# ProDoc_T527_LPDDR4_8__2024-06-06.net
KiCad netlist of a schematic drawn in EasyEDA Pro
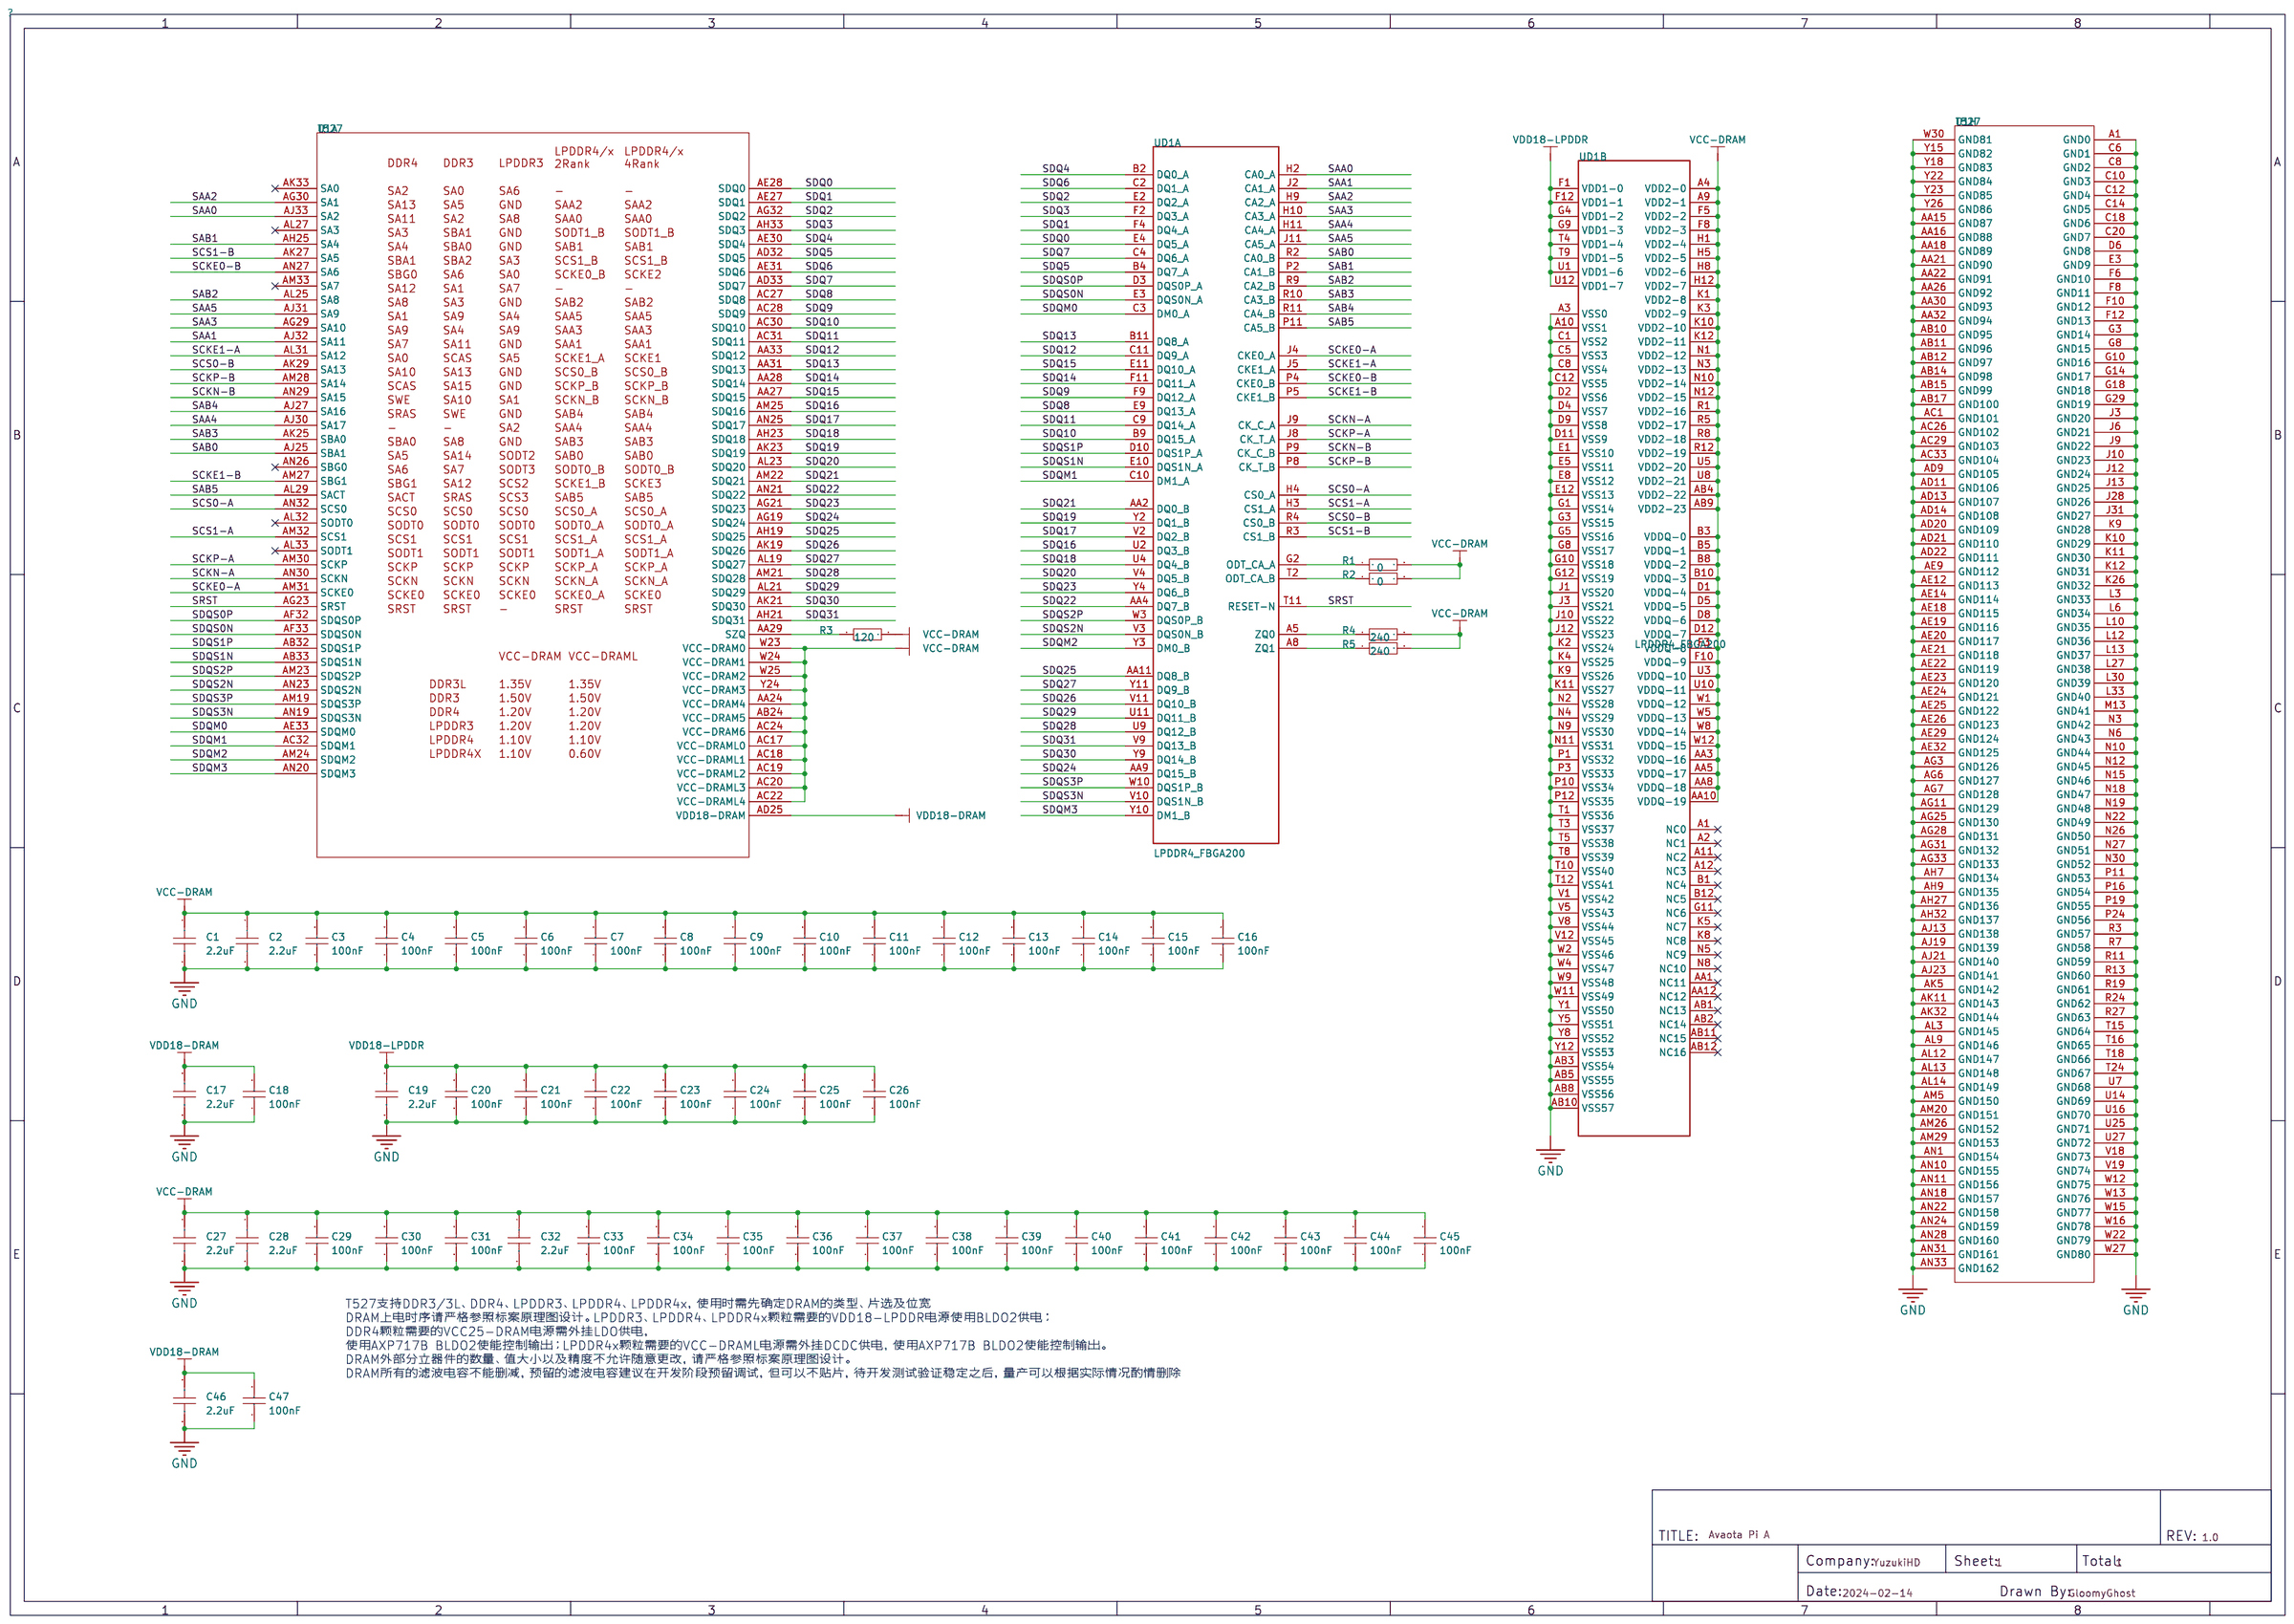
[diagram p0: schematic sheet]

(export (version "E")
  (design (tool "Eeschema 10.0.6"))
  (components
    (comp (ref "C1")
      (value "2.2uF")
      (footprint "easyedapro:C0201")
      (description "容值:2.2uF;精度:±20%;额定电压:6.3V;材质(温度系数):X5R;")
      (fields (field (name "Manufacturer Part") "0201X225M6R3NT") (field (name "Manufacturer") "FH(风华)"))
      (libsource (lib "easyedapro") (part "0201X225M6R3NT"))
    )
    (comp (ref "C2")
      (value "2.2uF")
      (footprint "easyedapro:C0201")
      (description "容值:2.2uF;精度:±20%;额定电压:6.3V;材质(温度系数):X5R;")
      (fields (field (name "Manufacturer Part") "0201X225M6R3NT") (field (name "Manufacturer") "FH(风华)"))
      (libsource (lib "easyedapro") (part "0201X225M6R3NT"))
    )
    (comp (ref "C3")
      (value "100nF")
      (footprint "easyedapro:C0201")
      (description "容值:100nF;精度:±10%;额定电压:10V;材质(温度系数):X5R;")
      (fields
        (field (name "Manufacturer Part") "GRM033R61A104KE15D")
        (field (name "Manufacturer") "muRata(村田)")
      )
      (libsource (lib "easyedapro") (part "GRM033R61A104KE15D"))
    )
    (comp (ref "C4")
      (value "100nF")
      (footprint "easyedapro:C0201")
      (description "容值:100nF;精度:±10%;额定电压:10V;材质(温度系数):X5R;")
      (fields
        (field (name "Manufacturer Part") "GRM033R61A104KE15D")
        (field (name "Manufacturer") "muRata(村田)")
      )
      (libsource (lib "easyedapro") (part "GRM033R61A104KE15D"))
    )
    (comp (ref "C5")
      (value "100nF")
      (footprint "easyedapro:C0201")
      (description "容值:100nF;精度:±10%;额定电压:10V;材质(温度系数):X5R;")
      (fields
        (field (name "Manufacturer Part") "GRM033R61A104KE15D")
        (field (name "Manufacturer") "muRata(村田)")
      )
      (libsource (lib "easyedapro") (part "GRM033R61A104KE15D"))
    )
    (comp (ref "C6")
      (value "100nF")
      (footprint "easyedapro:C0201")
      (description "容值:100nF;精度:±10%;额定电压:10V;材质(温度系数):X5R;")
      (fields
        (field (name "Manufacturer Part") "GRM033R61A104KE15D")
        (field (name "Manufacturer") "muRata(村田)")
      )
      (libsource (lib "easyedapro") (part "GRM033R61A104KE15D"))
    )
    (comp (ref "C7")
      (value "100nF")
      (footprint "easyedapro:C0201")
      (description "容值:100nF;精度:±10%;额定电压:10V;材质(温度系数):X5R;")
      (fields
        (field (name "Manufacturer Part") "GRM033R61A104KE15D")
        (field (name "Manufacturer") "muRata(村田)")
      )
      (libsource (lib "easyedapro") (part "GRM033R61A104KE15D"))
    )
    (comp (ref "C8")
      (value "100nF")
      (footprint "easyedapro:C0201")
      (description "容值:100nF;精度:±10%;额定电压:10V;材质(温度系数):X5R;")
      (fields
        (field (name "Manufacturer Part") "GRM033R61A104KE15D")
        (field (name "Manufacturer") "muRata(村田)")
      )
      (libsource (lib "easyedapro") (part "GRM033R61A104KE15D"))
    )
    (comp (ref "C9")
      (value "100nF")
      (footprint "easyedapro:C0201")
      (description "容值:100nF;精度:±10%;额定电压:10V;材质(温度系数):X5R;")
      (fields
        (field (name "Manufacturer Part") "GRM033R61A104KE15D")
        (field (name "Manufacturer") "muRata(村田)")
      )
      (libsource (lib "easyedapro") (part "GRM033R61A104KE15D"))
    )
    (comp (ref "C10")
      (value "100nF")
      (footprint "easyedapro:C0201")
      (description "容值:100nF;精度:±10%;额定电压:10V;材质(温度系数):X5R;")
      (fields
        (field (name "Manufacturer Part") "GRM033R61A104KE15D")
        (field (name "Manufacturer") "muRata(村田)")
      )
      (libsource (lib "easyedapro") (part "GRM033R61A104KE15D"))
    )
    (comp (ref "C11")
      (value "100nF")
      (footprint "easyedapro:C0201")
      (description "容值:100nF;精度:±10%;额定电压:10V;材质(温度系数):X5R;")
      (fields
        (field (name "Manufacturer Part") "GRM033R61A104KE15D")
        (field (name "Manufacturer") "muRata(村田)")
      )
      (libsource (lib "easyedapro") (part "GRM033R61A104KE15D"))
    )
    (comp (ref "C12")
      (value "100nF")
      (footprint "easyedapro:C0201")
      (description "容值:100nF;精度:±10%;额定电压:10V;材质(温度系数):X5R;")
      (fields
        (field (name "Manufacturer Part") "GRM033R61A104KE15D")
        (field (name "Manufacturer") "muRata(村田)")
      )
      (libsource (lib "easyedapro") (part "GRM033R61A104KE15D"))
    )
    (comp (ref "C13")
      (value "100nF")
      (footprint "easyedapro:C0201")
      (description "容值:100nF;精度:±10%;额定电压:10V;材质(温度系数):X5R;")
      (fields
        (field (name "Manufacturer Part") "GRM033R61A104KE15D")
        (field (name "Manufacturer") "muRata(村田)")
      )
      (libsource (lib "easyedapro") (part "GRM033R61A104KE15D"))
    )
    (comp (ref "C14")
      (value "100nF")
      (footprint "easyedapro:C0201")
      (description "容值:100nF;精度:±10%;额定电压:10V;材质(温度系数):X5R;")
      (fields
        (field (name "Manufacturer Part") "GRM033R61A104KE15D")
        (field (name "Manufacturer") "muRata(村田)")
      )
      (libsource (lib "easyedapro") (part "GRM033R61A104KE15D"))
    )
    (comp (ref "C15")
      (value "100nF")
      (footprint "easyedapro:C0201")
      (description "容值:100nF;精度:±10%;额定电压:10V;材质(温度系数):X5R;")
      (fields
        (field (name "Manufacturer Part") "GRM033R61A104KE15D")
        (field (name "Manufacturer") "muRata(村田)")
      )
      (libsource (lib "easyedapro") (part "GRM033R61A104KE15D"))
    )
    (comp (ref "C16")
      (value "100nF")
      (footprint "easyedapro:C0201")
      (description "容值:100nF;精度:±10%;额定电压:10V;材质(温度系数):X5R;")
      (fields
        (field (name "Manufacturer Part") "GRM033R61A104KE15D")
        (field (name "Manufacturer") "muRata(村田)")
      )
      (libsource (lib "easyedapro") (part "GRM033R61A104KE15D"))
    )
    (comp (ref "C17")
      (value "2.2uF")
      (footprint "easyedapro:C0201")
      (description "容值:2.2uF;精度:±20%;额定电压:6.3V;材质(温度系数):X5R;")
      (fields (field (name "Manufacturer Part") "0201X225M6R3NT") (field (name "Manufacturer") "FH(风华)"))
      (libsource (lib "easyedapro") (part "0201X225M6R3NT"))
    )
    (comp (ref "C18")
      (value "100nF")
      (footprint "easyedapro:C0201")
      (description "容值:100nF;精度:±10%;额定电压:10V;材质(温度系数):X5R;")
      (fields
        (field (name "Manufacturer Part") "GRM033R61A104KE15D")
        (field (name "Manufacturer") "muRata(村田)")
      )
      (libsource (lib "easyedapro") (part "GRM033R61A104KE15D"))
    )
    (comp (ref "C19")
      (value "2.2uF")
      (footprint "easyedapro:C0201")
      (description "容值:2.2uF;精度:±20%;额定电压:6.3V;材质(温度系数):X5R;")
      (fields (field (name "Manufacturer Part") "0201X225M6R3NT") (field (name "Manufacturer") "FH(风华)"))
      (libsource (lib "easyedapro") (part "0201X225M6R3NT"))
    )
    (comp (ref "C20")
      (value "100nF")
      (footprint "easyedapro:C0201")
      (description "容值:100nF;精度:±10%;额定电压:10V;材质(温度系数):X5R;")
      (fields
        (field (name "Manufacturer Part") "GRM033R61A104KE15D")
        (field (name "Manufacturer") "muRata(村田)")
      )
      (libsource (lib "easyedapro") (part "GRM033R61A104KE15D"))
    )
    (comp (ref "C21")
      (value "100nF")
      (footprint "easyedapro:C0201")
      (description "容值:100nF;精度:±10%;额定电压:10V;材质(温度系数):X5R;")
      (fields
        (field (name "Manufacturer Part") "GRM033R61A104KE15D")
        (field (name "Manufacturer") "muRata(村田)")
      )
      (libsource (lib "easyedapro") (part "GRM033R61A104KE15D"))
    )
    (comp (ref "C22")
      (value "100nF")
      (footprint "easyedapro:C0201")
      (description "容值:100nF;精度:±10%;额定电压:10V;材质(温度系数):X5R;")
      (fields
        (field (name "Manufacturer Part") "GRM033R61A104KE15D")
        (field (name "Manufacturer") "muRata(村田)")
      )
      (libsource (lib "easyedapro") (part "GRM033R61A104KE15D"))
    )
    (comp (ref "C23")
      (value "100nF")
      (footprint "easyedapro:C0201")
      (description "容值:100nF;精度:±10%;额定电压:10V;材质(温度系数):X5R;")
      (fields
        (field (name "Manufacturer Part") "GRM033R61A104KE15D")
        (field (name "Manufacturer") "muRata(村田)")
      )
      (libsource (lib "easyedapro") (part "GRM033R61A104KE15D"))
    )
    (comp (ref "C24")
      (value "100nF")
      (footprint "easyedapro:C0201")
      (description "容值:100nF;精度:±10%;额定电压:10V;材质(温度系数):X5R;")
      (fields
        (field (name "Manufacturer Part") "GRM033R61A104KE15D")
        (field (name "Manufacturer") "muRata(村田)")
      )
      (libsource (lib "easyedapro") (part "GRM033R61A104KE15D"))
    )
    (comp (ref "C25")
      (value "100nF")
      (footprint "easyedapro:C0201")
      (description "容值:100nF;精度:±10%;额定电压:10V;材质(温度系数):X5R;")
      (fields
        (field (name "Manufacturer Part") "GRM033R61A104KE15D")
        (field (name "Manufacturer") "muRata(村田)")
      )
      (libsource (lib "easyedapro") (part "GRM033R61A104KE15D"))
    )
    (comp (ref "C26")
      (value "100nF")
      (footprint "easyedapro:C0201")
      (description "容值:100nF;精度:±10%;额定电压:10V;材质(温度系数):X5R;")
      (fields
        (field (name "Manufacturer Part") "GRM033R61A104KE15D")
        (field (name "Manufacturer") "muRata(村田)")
      )
      (libsource (lib "easyedapro") (part "GRM033R61A104KE15D"))
    )
    (comp (ref "C27")
      (value "2.2uF")
      (footprint "easyedapro:C0201")
      (description "容值:2.2uF;精度:±20%;额定电压:6.3V;材质(温度系数):X5R;")
      (fields (field (name "Manufacturer Part") "0201X225M6R3NT") (field (name "Manufacturer") "FH(风华)"))
      (libsource (lib "easyedapro") (part "0201X225M6R3NT"))
    )
    (comp (ref "C28")
      (value "2.2uF")
      (footprint "easyedapro:C0201")
      (description "容值:2.2uF;精度:±20%;额定电压:6.3V;材质(温度系数):X5R;")
      (fields (field (name "Manufacturer Part") "0201X225M6R3NT") (field (name "Manufacturer") "FH(风华)"))
      (libsource (lib "easyedapro") (part "0201X225M6R3NT"))
    )
    (comp (ref "C29")
      (value "100nF")
      (footprint "easyedapro:C0201")
      (description "容值:100nF;精度:±10%;额定电压:10V;材质(温度系数):X5R;")
      (fields
        (field (name "Manufacturer Part") "GRM033R61A104KE15D")
        (field (name "Manufacturer") "muRata(村田)")
      )
      (libsource (lib "easyedapro") (part "GRM033R61A104KE15D"))
    )
    (comp (ref "C30")
      (value "100nF")
      (footprint "easyedapro:C0201")
      (description "容值:100nF;精度:±10%;额定电压:10V;材质(温度系数):X5R;")
      (fields
        (field (name "Manufacturer Part") "GRM033R61A104KE15D")
        (field (name "Manufacturer") "muRata(村田)")
      )
      (libsource (lib "easyedapro") (part "GRM033R61A104KE15D"))
    )
    (comp (ref "C31")
      (value "100nF")
      (footprint "easyedapro:C0201")
      (description "容值:100nF;精度:±10%;额定电压:10V;材质(温度系数):X5R;")
      (fields
        (field (name "Manufacturer Part") "GRM033R61A104KE15D")
        (field (name "Manufacturer") "muRata(村田)")
      )
      (libsource (lib "easyedapro") (part "GRM033R61A104KE15D"))
    )
    (comp (ref "C32")
      (value "2.2uF")
      (footprint "easyedapro:C0201")
      (description "容值:2.2uF;精度:±20%;额定电压:6.3V;材质(温度系数):X5R;")
      (fields (field (name "Manufacturer Part") "0201X225M6R3NT") (field (name "Manufacturer") "FH(风华)"))
      (libsource (lib "easyedapro") (part "0201X225M6R3NT"))
    )
    (comp (ref "C33")
      (value "100nF")
      (footprint "easyedapro:C0201")
      (description "容值:100nF;精度:±10%;额定电压:10V;材质(温度系数):X5R;")
      (fields
        (field (name "Manufacturer Part") "GRM033R61A104KE15D")
        (field (name "Manufacturer") "muRata(村田)")
      )
      (libsource (lib "easyedapro") (part "GRM033R61A104KE15D"))
    )
    (comp (ref "C34")
      (value "100nF")
      (footprint "easyedapro:C0201")
      (description "容值:100nF;精度:±10%;额定电压:10V;材质(温度系数):X5R;")
      (fields
        (field (name "Manufacturer Part") "GRM033R61A104KE15D")
        (field (name "Manufacturer") "muRata(村田)")
      )
      (libsource (lib "easyedapro") (part "GRM033R61A104KE15D"))
    )
    (comp (ref "C35")
      (value "100nF")
      (footprint "easyedapro:C0201")
      (description "容值:100nF;精度:±10%;额定电压:10V;材质(温度系数):X5R;")
      (fields
        (field (name "Manufacturer Part") "GRM033R61A104KE15D")
        (field (name "Manufacturer") "muRata(村田)")
      )
      (libsource (lib "easyedapro") (part "GRM033R61A104KE15D"))
    )
    (comp (ref "C36")
      (value "100nF")
      (footprint "easyedapro:C0201")
      (description "容值:100nF;精度:±10%;额定电压:10V;材质(温度系数):X5R;")
      (fields
        (field (name "Manufacturer Part") "GRM033R61A104KE15D")
        (field (name "Manufacturer") "muRata(村田)")
      )
      (libsource (lib "easyedapro") (part "GRM033R61A104KE15D"))
    )
    (comp (ref "C37")
      (value "100nF")
      (footprint "easyedapro:C0201")
      (description "容值:100nF;精度:±10%;额定电压:10V;材质(温度系数):X5R;")
      (fields
        (field (name "Manufacturer Part") "GRM033R61A104KE15D")
        (field (name "Manufacturer") "muRata(村田)")
      )
      (libsource (lib "easyedapro") (part "GRM033R61A104KE15D"))
    )
    (comp (ref "C38")
      (value "100nF")
      (footprint "easyedapro:C0201")
      (description "容值:100nF;精度:±10%;额定电压:10V;材质(温度系数):X5R;")
      (fields
        (field (name "Manufacturer Part") "GRM033R61A104KE15D")
        (field (name "Manufacturer") "muRata(村田)")
      )
      (libsource (lib "easyedapro") (part "GRM033R61A104KE15D"))
    )
    (comp (ref "C39")
      (value "100nF")
      (footprint "easyedapro:C0201")
      (description "容值:100nF;精度:±10%;额定电压:10V;材质(温度系数):X5R;")
      (fields
        (field (name "Manufacturer Part") "GRM033R61A104KE15D")
        (field (name "Manufacturer") "muRata(村田)")
      )
      (libsource (lib "easyedapro") (part "GRM033R61A104KE15D"))
    )
    (comp (ref "C40")
      (value "100nF")
      (footprint "easyedapro:C0201")
      (description "容值:100nF;精度:±10%;额定电压:10V;材质(温度系数):X5R;")
      (fields
        (field (name "Manufacturer Part") "GRM033R61A104KE15D")
        (field (name "Manufacturer") "muRata(村田)")
      )
      (libsource (lib "easyedapro") (part "GRM033R61A104KE15D"))
    )
    (comp (ref "C41")
      (value "100nF")
      (footprint "easyedapro:C0201")
      (description "容值:100nF;精度:±10%;额定电压:10V;材质(温度系数):X5R;")
      (fields
        (field (name "Manufacturer Part") "GRM033R61A104KE15D")
        (field (name "Manufacturer") "muRata(村田)")
      )
      (libsource (lib "easyedapro") (part "GRM033R61A104KE15D"))
    )
    (comp (ref "C42")
      (value "100nF")
      (footprint "easyedapro:C0201")
      (description "容值:100nF;精度:±10%;额定电压:10V;材质(温度系数):X5R;")
      (fields
        (field (name "Manufacturer Part") "GRM033R61A104KE15D")
        (field (name "Manufacturer") "muRata(村田)")
      )
      (libsource (lib "easyedapro") (part "GRM033R61A104KE15D"))
    )
    (comp (ref "C43")
      (value "100nF")
      (footprint "easyedapro:C0201")
      (description "容值:100nF;精度:±10%;额定电压:10V;材质(温度系数):X5R;")
      (fields
        (field (name "Manufacturer Part") "GRM033R61A104KE15D")
        (field (name "Manufacturer") "muRata(村田)")
      )
      (libsource (lib "easyedapro") (part "GRM033R61A104KE15D"))
    )
    (comp (ref "C44")
      (value "100nF")
      (footprint "easyedapro:C0201")
      (description "容值:100nF;精度:±10%;额定电压:10V;材质(温度系数):X5R;")
      (fields
        (field (name "Manufacturer Part") "GRM033R61A104KE15D")
        (field (name "Manufacturer") "muRata(村田)")
      )
      (libsource (lib "easyedapro") (part "GRM033R61A104KE15D"))
    )
    (comp (ref "C45")
      (value "100nF")
      (footprint "easyedapro:C0201")
      (description "容值:100nF;精度:±10%;额定电压:10V;材质(温度系数):X5R;")
      (fields
        (field (name "Manufacturer Part") "GRM033R61A104KE15D")
        (field (name "Manufacturer") "muRata(村田)")
      )
      (libsource (lib "easyedapro") (part "GRM033R61A104KE15D"))
    )
    (comp (ref "C46")
      (value "2.2uF")
      (footprint "easyedapro:C0201")
      (description "容值:2.2uF;精度:±20%;额定电压:6.3V;材质(温度系数):X5R;")
      (fields (field (name "Manufacturer Part") "0201X225M6R3NT") (field (name "Manufacturer") "FH(风华)"))
      (libsource (lib "easyedapro") (part "0201X225M6R3NT"))
    )
    (comp (ref "C47")
      (value "100nF")
      (footprint "easyedapro:C0201")
      (description "容值:100nF;精度:±10%;额定电压:10V;材质(温度系数):X5R;")
      (fields
        (field (name "Manufacturer Part") "GRM033R61A104KE15D")
        (field (name "Manufacturer") "muRata(村田)")
      )
      (libsource (lib "easyedapro") (part "GRM033R61A104KE15D"))
    )
    (comp (ref "R1") (value "0") (footprint "easyedapro:R0201") (libsource (lib "easyedapro") (part "电阻")))
    (comp (ref "R2") (value "0") (footprint "easyedapro:R0201") (libsource (lib "easyedapro") (part "电阻")))
    (comp (ref "R3") (value "120") (footprint "easyedapro:R0201") (libsource (lib "easyedapro") (part "电阻")))
    (comp (ref "R4") (value "240") (footprint "easyedapro:R0201") (libsource (lib "easyedapro") (part "电阻")))
    (comp (ref "R5") (value "240") (footprint "easyedapro:R0201") (libsource (lib "easyedapro") (part "电阻")))
    (comp (ref "U1")
      (value "T527")
      (footprint "easyedapro:T527-BGA664")
      (description "Allwinner T527 SoC")
      (libsource (lib "easyedapro") (part "T527"))
    )
    (comp (ref "UD1")
      (value "LPDDR4_FBGA200")
      (footprint "easyedapro:BGA200P65_80B1000_1500H90")
      (libsource (lib "easyedapro") (part "LPDDR4_FBGA200"))
    )
  )
  (nets
    (net (code "1") (name "/SAA0") (class "Default")
      (node (ref "U1") (pin "AJ33") (pinfunction "SA2_AJ33") (pintype "input"))
      (node (ref "UD1") (pin "H2") (pinfunction "CA0_A_H2") (pintype "input"))
    )
    (net (code "2") (name "/SAA1") (class "Default")
      (node (ref "U1") (pin "AJ32") (pinfunction "SA11_AJ32") (pintype "input"))
      (node (ref "UD1") (pin "J2") (pinfunction "CA1_A_J2") (pintype "input"))
    )
    (net (code "3") (name "/SAA2") (class "Default")
      (node (ref "U1") (pin "AG30") (pinfunction "SA1_AG30") (pintype "input"))
      (node (ref "UD1") (pin "H9") (pinfunction "CA2_A_H9") (pintype "input"))
    )
    (net (code "4") (name "/SAA3") (class "Default")
      (node (ref "U1") (pin "AG29") (pinfunction "SA10_AG29") (pintype "input"))
      (node (ref "UD1") (pin "H10") (pinfunction "CA3_A_H10") (pintype "input"))
    )
    (net (code "5") (name "/SAA4") (class "Default")
      (node (ref "U1") (pin "AJ30") (pinfunction "SA17_AJ30") (pintype "input"))
      (node (ref "UD1") (pin "H11") (pinfunction "CA4_A_H11") (pintype "input"))
    )
    (net (code "6") (name "/SAA5") (class "Default")
      (node (ref "U1") (pin "AJ31") (pinfunction "SA9_AJ31") (pintype "input"))
      (node (ref "UD1") (pin "J11") (pinfunction "CA5_A_J11") (pintype "input"))
    )
    (net (code "7") (name "/SAB0") (class "Default")
      (node (ref "U1") (pin "AJ25") (pinfunction "SBA1_AJ25") (pintype "input"))
      (node (ref "UD1") (pin "R2") (pinfunction "CA0_B_R2") (pintype "input"))
    )
    (net (code "8") (name "/SAB1") (class "Default")
      (node (ref "U1") (pin "AH25") (pinfunction "SA4_AH25") (pintype "input"))
      (node (ref "UD1") (pin "P2") (pinfunction "CA1_B_P2") (pintype "input"))
    )
    (net (code "9") (name "/SAB2") (class "Default")
      (node (ref "U1") (pin "AL25") (pinfunction "SA8_AL25") (pintype "input"))
      (node (ref "UD1") (pin "R9") (pinfunction "CA2_B_R9") (pintype "input"))
    )
    (net (code "10") (name "/SAB3") (class "Default")
      (node (ref "U1") (pin "AK25") (pinfunction "SBA0_AK25") (pintype "input"))
      (node (ref "UD1") (pin "R10") (pinfunction "CA3_B_R10") (pintype "input"))
    )
    (net (code "11") (name "/SAB4") (class "Default")
      (node (ref "U1") (pin "AJ27") (pinfunction "SA16_AJ27") (pintype "input"))
      (node (ref "UD1") (pin "R11") (pinfunction "CA4_B_R11") (pintype "input"))
    )
    (net (code "12") (name "/SAB5") (class "Default")
      (node (ref "U1") (pin "AL29") (pinfunction "SACT_AL29") (pintype "input"))
      (node (ref "UD1") (pin "P11") (pinfunction "CA5_B_P11") (pintype "input"))
    )
    (net (code "13") (name "/SCKE0-A") (class "Default")
      (node (ref "U1") (pin "AM31") (pinfunction "SCKE0_AM31") (pintype "input"))
      (node (ref "UD1") (pin "J4") (pinfunction "CKE0_A_J4") (pintype "input"))
    )
    (net (code "14") (name "/SCKE0-B") (class "Default")
      (node (ref "U1") (pin "AN27") (pinfunction "SA6_AN27") (pintype "input"))
      (node (ref "UD1") (pin "P4") (pinfunction "CKE0_B_P4") (pintype "input"))
    )
    (net (code "15") (name "/SCKE1-A") (class "Default")
      (node (ref "U1") (pin "AL31") (pinfunction "SA12_AL31") (pintype "input"))
      (node (ref "UD1") (pin "J5") (pinfunction "CKE1_A_J5") (pintype "input"))
    )
    (net (code "16") (name "/SCKE1-B") (class "Default")
      (node (ref "U1") (pin "AM27") (pinfunction "SBG1_AM27") (pintype "input"))
      (node (ref "UD1") (pin "P5") (pinfunction "CKE1_B_P5") (pintype "input"))
    )
    (net (code "17") (name "/SCKN-A") (class "Default")
      (node (ref "U1") (pin "AN30") (pinfunction "SCKN_AN30") (pintype "input"))
      (node (ref "UD1") (pin "J9") (pinfunction "CK_C_A_J9") (pintype "input"))
    )
    (net (code "18") (name "/SCKN-B") (class "Default")
      (node (ref "U1") (pin "AN29") (pinfunction "SA15_AN29") (pintype "input"))
      (node (ref "UD1") (pin "P9") (pinfunction "CK_C_B_P9") (pintype "input"))
    )
    (net (code "19") (name "/SCKP-A") (class "Default")
      (node (ref "U1") (pin "AM30") (pinfunction "SCKP_AM30") (pintype "input"))
      (node (ref "UD1") (pin "J8") (pinfunction "CK_T_A_J8") (pintype "input"))
    )
    (net (code "20") (name "/SCKP-B") (class "Default")
      (node (ref "U1") (pin "AM28") (pinfunction "SA14_AM28") (pintype "input"))
      (node (ref "UD1") (pin "P8") (pinfunction "CK_T_B_P8") (pintype "input"))
    )
    (net (code "21") (name "/SCS0-A") (class "Default")
      (node (ref "U1") (pin "AN32") (pinfunction "SCS0_AN32") (pintype "input"))
      (node (ref "UD1") (pin "H4") (pinfunction "CS0_A_H4") (pintype "input"))
    )
    (net (code "22") (name "/SCS0-B") (class "Default")
      (node (ref "U1") (pin "AK29") (pinfunction "SA13_AK29") (pintype "input"))
      (node (ref "UD1") (pin "R4") (pinfunction "CS0_B_R4") (pintype "input"))
    )
    (net (code "23") (name "/SCS1-A") (class "Default")
      (node (ref "U1") (pin "AM32") (pinfunction "SCS1_AM32") (pintype "input"))
      (node (ref "UD1") (pin "H3") (pinfunction "CS1_A_H3") (pintype "input"))
    )
    (net (code "24") (name "/SCS1-B") (class "Default")
      (node (ref "U1") (pin "AK27") (pinfunction "SA5_AK27") (pintype "input"))
      (node (ref "UD1") (pin "R3") (pinfunction "CS1_B_R3") (pintype "input"))
    )
    (net (code "25") (name "/SDQ0") (class "Default")
      (node (ref "U1") (pin "AE28") (pinfunction "SDQ0_AE28") (pintype "input"))
      (node (ref "UD1") (pin "E4") (pinfunction "DQ5_A_E4") (pintype "input"))
    )
    (net (code "26") (name "/SDQ1") (class "Default")
      (node (ref "U1") (pin "AE27") (pinfunction "SDQ1_AE27") (pintype "input"))
      (node (ref "UD1") (pin "F4") (pinfunction "DQ4_A_F4") (pintype "input"))
    )
    (net (code "27") (name "/SDQ2") (class "Default")
      (node (ref "U1") (pin "AG32") (pinfunction "SDQ2_AG32") (pintype "input"))
      (node (ref "UD1") (pin "E2") (pinfunction "DQ2_A_E2") (pintype "input"))
    )
    (net (code "28") (name "/SDQ3") (class "Default")
      (node (ref "U1") (pin "AH33") (pinfunction "SDQ3_AH33") (pintype "input"))
      (node (ref "UD1") (pin "F2") (pinfunction "DQ3_A_F2") (pintype "input"))
    )
    (net (code "29") (name "/SDQ4") (class "Default")
      (node (ref "U1") (pin "AE30") (pinfunction "SDQ4_AE30") (pintype "input"))
      (node (ref "UD1") (pin "B2") (pinfunction "DQ0_A_B2") (pintype "input"))
    )
    (net (code "30") (name "/SDQ5") (class "Default")
      (node (ref "U1") (pin "AD32") (pinfunction "SDQ5_AD32") (pintype "input"))
      (node (ref "UD1") (pin "B4") (pinfunction "DQ7_A_B4") (pintype "input"))
    )
    (net (code "31") (name "/SDQ6") (class "Default")
      (node (ref "U1") (pin "AE31") (pinfunction "SDQ6_AE31") (pintype "input"))
      (node (ref "UD1") (pin "C2") (pinfunction "DQ1_A_C2") (pintype "input"))
    )
    (net (code "32") (name "/SDQ7") (class "Default")
      (node (ref "U1") (pin "AD33") (pinfunction "SDQ7_AD33") (pintype "input"))
      (node (ref "UD1") (pin "C4") (pinfunction "DQ6_A_C4") (pintype "input"))
    )
    (net (code "33") (name "/SDQ8") (class "Default")
      (node (ref "U1") (pin "AC27") (pinfunction "SDQ8_AC27") (pintype "input"))
      (node (ref "UD1") (pin "E9") (pinfunction "DQ13_A_E9") (pintype "input"))
    )
    (net (code "34") (name "/SDQ9") (class "Default")
      (node (ref "U1") (pin "AC28") (pinfunction "SDQ9_AC28") (pintype "input"))
      (node (ref "UD1") (pin "F9") (pinfunction "DQ12_A_F9") (pintype "input"))
    )
    (net (code "35") (name "/SDQ10") (class "Default")
      (node (ref "U1") (pin "AC30") (pinfunction "SDQ10_AC30") (pintype "input"))
      (node (ref "UD1") (pin "B9") (pinfunction "DQ15_A_B9") (pintype "input"))
    )
    (net (code "36") (name "/SDQ11") (class "Default")
      (node (ref "U1") (pin "AC31") (pinfunction "SDQ11_AC31") (pintype "input"))
      (node (ref "UD1") (pin "C9") (pinfunction "DQ14_A_C9") (pintype "input"))
    )
    (net (code "37") (name "/SDQ12") (class "Default")
      (node (ref "U1") (pin "AA33") (pinfunction "SDQ12_AA33") (pintype "input"))
      (node (ref "UD1") (pin "C11") (pinfunction "DQ9_A_C11") (pintype "input"))
    )
    (net (code "38") (name "/SDQ13") (class "Default")
      (node (ref "U1") (pin "AA31") (pinfunction "SDQ13_AA31") (pintype "input"))
      (node (ref "UD1") (pin "B11") (pinfunction "DQ8_A_B11") (pintype "input"))
    )
    (net (code "39") (name "/SDQ14") (class "Default")
      (node (ref "U1") (pin "AA28") (pinfunction "SDQ14_AA28") (pintype "input"))
      (node (ref "UD1") (pin "F11") (pinfunction "DQ11_A_F11") (pintype "input"))
    )
    (net (code "40") (name "/SDQ15") (class "Default")
      (node (ref "U1") (pin "AA27") (pinfunction "SDQ15_AA27") (pintype "input"))
      (node (ref "UD1") (pin "E11") (pinfunction "DQ10_A_E11") (pintype "input"))
    )
    (net (code "41") (name "/SDQ16") (class "Default")
      (node (ref "U1") (pin "AM25") (pinfunction "SDQ16_AM25") (pintype "input"))
      (node (ref "UD1") (pin "U2") (pinfunction "DQ3_B_U2") (pintype "input"))
    )
    (net (code "42") (name "/SDQ17") (class "Default")
      (node (ref "U1") (pin "AN25") (pinfunction "SDQ17_AN25") (pintype "input"))
      (node (ref "UD1") (pin "V2") (pinfunction "DQ2_B_V2") (pintype "input"))
    )
    (net (code "43") (name "/SDQ18") (class "Default")
      (node (ref "U1") (pin "AH23") (pinfunction "SDQ18_AH23") (pintype "input"))
      (node (ref "UD1") (pin "U4") (pinfunction "DQ4_B_U4") (pintype "input"))
    )
    (net (code "44") (name "/SDQ19") (class "Default")
      (node (ref "U1") (pin "AK23") (pinfunction "SDQ19_AK23") (pintype "input"))
      (node (ref "UD1") (pin "Y2") (pinfunction "DQ1_B_Y2") (pintype "input"))
    )
    (net (code "45") (name "/SDQ20") (class "Default")
      (node (ref "U1") (pin "AL23") (pinfunction "SDQ20_AL23") (pintype "input"))
      (node (ref "UD1") (pin "V4") (pinfunction "DQ5_B_V4") (pintype "input"))
    )
    (net (code "46") (name "/SDQ21") (class "Default")
      (node (ref "U1") (pin "AM22") (pinfunction "SDQ21_AM22") (pintype "input"))
      (node (ref "UD1") (pin "AA2") (pinfunction "DQ0_B_AA2") (pintype "input"))
    )
    (net (code "47") (name "/SDQ22") (class "Default")
      (node (ref "U1") (pin "AN21") (pinfunction "SDQ22_AN21") (pintype "input"))
      (node (ref "UD1") (pin "AA4") (pinfunction "DQ7_B_AA4") (pintype "input"))
    )
    (net (code "48") (name "/SDQ23") (class "Default")
      (node (ref "U1") (pin "AG21") (pinfunction "SDQ23_AG21") (pintype "input"))
      (node (ref "UD1") (pin "Y4") (pinfunction "DQ6_B_Y4") (pintype "input"))
    )
    (net (code "49") (name "/SDQ24") (class "Default")
      (node (ref "U1") (pin "AG19") (pinfunction "SDQ24_AG19") (pintype "input"))
      (node (ref "UD1") (pin "AA9") (pinfunction "DQ15_B_AA9") (pintype "input"))
    )
    (net (code "50") (name "/SDQ25") (class "Default")
      (node (ref "U1") (pin "AH19") (pinfunction "SDQ25_AH19") (pintype "input"))
      (node (ref "UD1") (pin "AA11") (pinfunction "DQ8_B_AA11") (pintype "input"))
    )
    (net (code "51") (name "/SDQ26") (class "Default")
      (node (ref "U1") (pin "AK19") (pinfunction "SDQ26_AK19") (pintype "input"))
      (node (ref "UD1") (pin "V11") (pinfunction "DQ10_B_V11") (pintype "input"))
    )
    (net (code "52") (name "/SDQ27") (class "Default")
      (node (ref "U1") (pin "AL19") (pinfunction "SDQ27_AL19") (pintype "input"))
      (node (ref "UD1") (pin "Y11") (pinfunction "DQ9_B_Y11") (pintype "input"))
    )
    (net (code "53") (name "/SDQ28") (class "Default")
      (node (ref "U1") (pin "AM21") (pinfunction "SDQ28_AM21") (pintype "input"))
      (node (ref "UD1") (pin "U9") (pinfunction "DQ12_B_U9") (pintype "input"))
    )
    (net (code "54") (name "/SDQ29") (class "Default")
      (node (ref "U1") (pin "AL21") (pinfunction "SDQ29_AL21") (pintype "input"))
      (node (ref "UD1") (pin "U11") (pinfunction "DQ11_B_U11") (pintype "input"))
    )
    (net (code "55") (name "/SDQ30") (class "Default")
      (node (ref "U1") (pin "AK21") (pinfunction "SDQ30_AK21") (pintype "input"))
      (node (ref "UD1") (pin "Y9") (pinfunction "DQ14_B_Y9") (pintype "input"))
    )
    (net (code "56") (name "/SDQ31") (class "Default")
      (node (ref "U1") (pin "AH21") (pinfunction "SDQ31_AH21") (pintype "input"))
      (node (ref "UD1") (pin "V9") (pinfunction "DQ13_B_V9") (pintype "input"))
    )
    (net (code "57") (name "/SDQM0") (class "Default")
      (node (ref "U1") (pin "AE33") (pinfunction "SDQM0_AE33") (pintype "input"))
      (node (ref "UD1") (pin "C3") (pinfunction "DM0_A_C3") (pintype "input"))
    )
    (net (code "58") (name "/SDQM1") (class "Default")
      (node (ref "U1") (pin "AC32") (pinfunction "SDQM1_AC32") (pintype "input"))
      (node (ref "UD1") (pin "C10") (pinfunction "DM1_A_C10") (pintype "input"))
    )
    (net (code "59") (name "/SDQM2") (class "Default")
      (node (ref "U1") (pin "AM24") (pinfunction "SDQM2_AM24") (pintype "input"))
      (node (ref "UD1") (pin "Y3") (pinfunction "DM0_B_Y3") (pintype "input"))
    )
    (net (code "60") (name "/SDQM3") (class "Default")
      (node (ref "U1") (pin "AN20") (pinfunction "SDQM3_AN20") (pintype "input"))
      (node (ref "UD1") (pin "Y10") (pinfunction "DM1_B_Y10") (pintype "input"))
    )
    (net (code "61") (name "/SDQS0N") (class "Default")
      (node (ref "U1") (pin "AF33") (pinfunction "SDQS0N_AF33") (pintype "input"))
      (node (ref "UD1") (pin "E3") (pinfunction "DQS0N_A_E3") (pintype "input"))
    )
    (net (code "62") (name "/SDQS0P") (class "Default")
      (node (ref "U1") (pin "AF32") (pinfunction "SDQS0P_AF32") (pintype "input"))
      (node (ref "UD1") (pin "D3") (pinfunction "DQS0P_A_D3") (pintype "input"))
    )
    (net (code "63") (name "/SDQS1N") (class "Default")
      (node (ref "U1") (pin "AB33") (pinfunction "SDQS1N_AB33") (pintype "input"))
      (node (ref "UD1") (pin "E10") (pinfunction "DQS1N_A_E10") (pintype "input"))
    )
    (net (code "64") (name "/SDQS1P") (class "Default")
      (node (ref "U1") (pin "AB32") (pinfunction "SDQS1P_AB32") (pintype "input"))
      (node (ref "UD1") (pin "D10") (pinfunction "DQS1P_A_D10") (pintype "input"))
    )
    (net (code "65") (name "/SDQS2N") (class "Default")
      (node (ref "U1") (pin "AN23") (pinfunction "SDQS2N_AN23") (pintype "input"))
      (node (ref "UD1") (pin "V3") (pinfunction "DQS0N_B_V3") (pintype "input"))
    )
    (net (code "66") (name "/SDQS2P") (class "Default")
      (node (ref "U1") (pin "AM23") (pinfunction "SDQS2P_AM23") (pintype "input"))
      (node (ref "UD1") (pin "W3") (pinfunction "DQS0P_B_W3") (pintype "input"))
    )
    (net (code "67") (name "/SDQS3N") (class "Default")
      (node (ref "U1") (pin "AN19") (pinfunction "SDQS3N_AN19") (pintype "input"))
      (node (ref "UD1") (pin "V10") (pinfunction "DQS1N_B_V10") (pintype "input"))
    )
    (net (code "68") (name "/SDQS3P") (class "Default")
      (node (ref "U1") (pin "AM19") (pinfunction "SDQS3P_AM19") (pintype "input"))
      (node (ref "UD1") (pin "W10") (pinfunction "DQS1P_B_W10") (pintype "input"))
    )
    (net (code "69") (name "/SRST") (class "Default")
      (node (ref "U1") (pin "AG23") (pinfunction "SRST_AG23") (pintype "input"))
      (node (ref "UD1") (pin "T11") (pinfunction "RESET-N_T11") (pintype "input"))
    )
    (net (code "70") (name "GND") (class "Default")
      (node (ref "C1") (pin "2") (pinfunction "2_2") (pintype "input"))
      (node (ref "C10") (pin "1") (pinfunction "1_1") (pintype "input"))
      (node (ref "C11") (pin "1") (pinfunction "1_1") (pintype "input"))
      (node (ref "C12") (pin "1") (pinfunction "1_1") (pintype "input"))
      (node (ref "C13") (pin "1") (pinfunction "1_1") (pintype "input"))
      (node (ref "C14") (pin "1") (pinfunction "1_1") (pintype "input"))
      (node (ref "C15") (pin "1") (pinfunction "1_1") (pintype "input"))
      (node (ref "C16") (pin "1") (pinfunction "1_1") (pintype "input"))
      (node (ref "C17") (pin "2") (pinfunction "2_2") (pintype "input"))
      (node (ref "C18") (pin "1") (pinfunction "1_1") (pintype "input"))
      (node (ref "C19") (pin "2") (pinfunction "2_2") (pintype "input"))
      (node (ref "C2") (pin "2") (pinfunction "2_2") (pintype "input"))
      (node (ref "C20") (pin "1") (pinfunction "1_1") (pintype "input"))
      (node (ref "C21") (pin "1") (pinfunction "1_1") (pintype "input"))
      (node (ref "C22") (pin "1") (pinfunction "1_1") (pintype "input"))
      (node (ref "C23") (pin "1") (pinfunction "1_1") (pintype "input"))
      (node (ref "C24") (pin "1") (pinfunction "1_1") (pintype "input"))
      (node (ref "C25") (pin "1") (pinfunction "1_1") (pintype "input"))
      (node (ref "C26") (pin "1") (pinfunction "1_1") (pintype "input"))
      (node (ref "C27") (pin "2") (pinfunction "2_2") (pintype "input"))
      (node (ref "C28") (pin "2") (pinfunction "2_2") (pintype "input"))
      (node (ref "C29") (pin "1") (pinfunction "1_1") (pintype "input"))
      (node (ref "C3") (pin "1") (pinfunction "1_1") (pintype "input"))
      (node (ref "C30") (pin "1") (pinfunction "1_1") (pintype "input"))
      (node (ref "C31") (pin "1") (pinfunction "1_1") (pintype "input"))
      (node (ref "C32") (pin "2") (pinfunction "2_2") (pintype "input"))
      (node (ref "C33") (pin "1") (pinfunction "1_1") (pintype "input"))
      (node (ref "C34") (pin "1") (pinfunction "1_1") (pintype "input"))
      (node (ref "C35") (pin "1") (pinfunction "1_1") (pintype "input"))
      (node (ref "C36") (pin "1") (pinfunction "1_1") (pintype "input"))
      (node (ref "C37") (pin "1") (pinfunction "1_1") (pintype "input"))
      (node (ref "C38") (pin "1") (pinfunction "1_1") (pintype "input"))
      (node (ref "C39") (pin "1") (pinfunction "1_1") (pintype "input"))
      (node (ref "C4") (pin "1") (pinfunction "1_1") (pintype "input"))
      (node (ref "C40") (pin "1") (pinfunction "1_1") (pintype "input"))
      (node (ref "C41") (pin "1") (pinfunction "1_1") (pintype "input"))
      (node (ref "C42") (pin "1") (pinfunction "1_1") (pintype "input"))
      (node (ref "C43") (pin "1") (pinfunction "1_1") (pintype "input"))
      (node (ref "C44") (pin "1") (pinfunction "1_1") (pintype "input"))
      (node (ref "C45") (pin "1") (pinfunction "1_1") (pintype "input"))
      (node (ref "C46") (pin "2") (pinfunction "2_2") (pintype "input"))
      (node (ref "C47") (pin "1") (pinfunction "1_1") (pintype "input"))
      (node (ref "C5") (pin "1") (pinfunction "1_1") (pintype "input"))
      (node (ref "C6") (pin "1") (pinfunction "1_1") (pintype "input"))
      (node (ref "C7") (pin "1") (pinfunction "1_1") (pintype "input"))
      (node (ref "C8") (pin "1") (pinfunction "1_1") (pintype "input"))
      (node (ref "C9") (pin "1") (pinfunction "1_1") (pintype "input"))
      (node (ref "U1") (pin "A1") (pinfunction "GND0_A1") (pintype "input"))
      (node (ref "U1") (pin "AA15") (pinfunction "GND87_AA15") (pintype "input"))
      (node (ref "U1") (pin "AA16") (pinfunction "GND88_AA16") (pintype "input"))
      (node (ref "U1") (pin "AA18") (pinfunction "GND89_AA18") (pintype "input"))
      (node (ref "U1") (pin "AA21") (pinfunction "GND90_AA21") (pintype "input"))
      (node (ref "U1") (pin "AA22") (pinfunction "GND91_AA22") (pintype "input"))
      (node (ref "U1") (pin "AA26") (pinfunction "GND92_AA26") (pintype "input"))
      (node (ref "U1") (pin "AA30") (pinfunction "GND93_AA30") (pintype "input"))
      (node (ref "U1") (pin "AA32") (pinfunction "GND94_AA32") (pintype "input"))
      (node (ref "U1") (pin "AB10") (pinfunction "GND95_AB10") (pintype "input"))
      (node (ref "U1") (pin "AB11") (pinfunction "GND96_AB11") (pintype "input"))
      (node (ref "U1") (pin "AB12") (pinfunction "GND97_AB12") (pintype "input"))
      (node (ref "U1") (pin "AB14") (pinfunction "GND98_AB14") (pintype "input"))
      (node (ref "U1") (pin "AB15") (pinfunction "GND99_AB15") (pintype "input"))
      (node (ref "U1") (pin "AB17") (pinfunction "GND100_AB17") (pintype "input"))
      (node (ref "U1") (pin "AC1") (pinfunction "GND101_AC1") (pintype "input"))
      (node (ref "U1") (pin "AC26") (pinfunction "GND102_AC26") (pintype "input"))
      (node (ref "U1") (pin "AC29") (pinfunction "GND103_AC29") (pintype "input"))
      (node (ref "U1") (pin "AC33") (pinfunction "GND104_AC33") (pintype "input"))
      (node (ref "U1") (pin "AD11") (pinfunction "GND106_AD11") (pintype "input"))
      (node (ref "U1") (pin "AD13") (pinfunction "GND107_AD13") (pintype "input"))
      (node (ref "U1") (pin "AD14") (pinfunction "GND108_AD14") (pintype "input"))
      (node (ref "U1") (pin "AD20") (pinfunction "GND109_AD20") (pintype "input"))
      (node (ref "U1") (pin "AD21") (pinfunction "GND110_AD21") (pintype "input"))
      (node (ref "U1") (pin "AD22") (pinfunction "GND111_AD22") (pintype "input"))
      (node (ref "U1") (pin "AD9") (pinfunction "GND105_AD9") (pintype "input"))
      (node (ref "U1") (pin "AE12") (pinfunction "GND113_AE12") (pintype "input"))
      (node (ref "U1") (pin "AE14") (pinfunction "GND114_AE14") (pintype "input"))
      (node (ref "U1") (pin "AE18") (pinfunction "GND115_AE18") (pintype "input"))
      (node (ref "U1") (pin "AE19") (pinfunction "GND116_AE19") (pintype "input"))
      (node (ref "U1") (pin "AE20") (pinfunction "GND117_AE20") (pintype "input"))
      (node (ref "U1") (pin "AE21") (pinfunction "GND118_AE21") (pintype "input"))
      (node (ref "U1") (pin "AE22") (pinfunction "GND119_AE22") (pintype "input"))
      (node (ref "U1") (pin "AE23") (pinfunction "GND120_AE23") (pintype "input"))
      (node (ref "U1") (pin "AE24") (pinfunction "GND121_AE24") (pintype "input"))
      (node (ref "U1") (pin "AE25") (pinfunction "GND122_AE25") (pintype "input"))
      (node (ref "U1") (pin "AE26") (pinfunction "GND123_AE26") (pintype "input"))
      (node (ref "U1") (pin "AE29") (pinfunction "GND124_AE29") (pintype "input"))
      (node (ref "U1") (pin "AE32") (pinfunction "GND125_AE32") (pintype "input"))
      (node (ref "U1") (pin "AE9") (pinfunction "GND112_AE9") (pintype "input"))
      (node (ref "U1") (pin "AG11") (pinfunction "GND129_AG11") (pintype "input"))
      (node (ref "U1") (pin "AG25") (pinfunction "GND130_AG25") (pintype "input"))
      (node (ref "U1") (pin "AG28") (pinfunction "GND131_AG28") (pintype "input"))
      (node (ref "U1") (pin "AG3") (pinfunction "GND126_AG3") (pintype "input"))
      (node (ref "U1") (pin "AG31") (pinfunction "GND132_AG31") (pintype "input"))
      (node (ref "U1") (pin "AG33") (pinfunction "GND133_AG33") (pintype "input"))
      (node (ref "U1") (pin "AG6") (pinfunction "GND127_AG6") (pintype "input"))
      (node (ref "U1") (pin "AG7") (pinfunction "GND128_AG7") (pintype "input"))
      (node (ref "U1") (pin "AH27") (pinfunction "GND136_AH27") (pintype "input"))
      (node (ref "U1") (pin "AH32") (pinfunction "GND137_AH32") (pintype "input"))
      (node (ref "U1") (pin "AH7") (pinfunction "GND134_AH7") (pintype "input"))
      (node (ref "U1") (pin "AH9") (pinfunction "GND135_AH9") (pintype "input"))
      (node (ref "U1") (pin "AJ13") (pinfunction "GND138_AJ13") (pintype "input"))
      (node (ref "U1") (pin "AJ19") (pinfunction "GND139_AJ19") (pintype "input"))
      (node (ref "U1") (pin "AJ21") (pinfunction "GND140_AJ21") (pintype "input"))
      (node (ref "U1") (pin "AJ23") (pinfunction "GND141_AJ23") (pintype "input"))
      (node (ref "U1") (pin "AK11") (pinfunction "GND143_AK11") (pintype "input"))
      (node (ref "U1") (pin "AK32") (pinfunction "GND144_AK32") (pintype "input"))
      (node (ref "U1") (pin "AK5") (pinfunction "GND142_AK5") (pintype "input"))
      (node (ref "U1") (pin "AL12") (pinfunction "GND147_AL12") (pintype "input"))
      (node (ref "U1") (pin "AL13") (pinfunction "GND148_AL13") (pintype "input"))
      (node (ref "U1") (pin "AL14") (pinfunction "GND149_AL14") (pintype "input"))
      (node (ref "U1") (pin "AL3") (pinfunction "GND145_AL3") (pintype "input"))
      (node (ref "U1") (pin "AL9") (pinfunction "GND146_AL9") (pintype "input"))
      (node (ref "U1") (pin "AM20") (pinfunction "GND151_AM20") (pintype "input"))
      (node (ref "U1") (pin "AM26") (pinfunction "GND152_AM26") (pintype "input"))
      (node (ref "U1") (pin "AM29") (pinfunction "GND153_AM29") (pintype "input"))
      (node (ref "U1") (pin "AM5") (pinfunction "GND150_AM5") (pintype "input"))
      (node (ref "U1") (pin "AN1") (pinfunction "GND154_AN1") (pintype "input"))
      (node (ref "U1") (pin "AN10") (pinfunction "GND155_AN10") (pintype "input"))
      (node (ref "U1") (pin "AN11") (pinfunction "GND156_AN11") (pintype "input"))
      (node (ref "U1") (pin "AN18") (pinfunction "GND157_AN18") (pintype "input"))
      (node (ref "U1") (pin "AN22") (pinfunction "GND158_AN22") (pintype "input"))
      (node (ref "U1") (pin "AN24") (pinfunction "GND159_AN24") (pintype "input"))
      (node (ref "U1") (pin "AN28") (pinfunction "GND160_AN28") (pintype "input"))
      (node (ref "U1") (pin "AN31") (pinfunction "GND161_AN31") (pintype "input"))
      (node (ref "U1") (pin "AN33") (pinfunction "GND162_AN33") (pintype "input"))
      (node (ref "U1") (pin "C10") (pinfunction "GND3_C10") (pintype "input"))
      (node (ref "U1") (pin "C12") (pinfunction "GND4_C12") (pintype "input"))
      (node (ref "U1") (pin "C14") (pinfunction "GND5_C14") (pintype "input"))
      (node (ref "U1") (pin "C18") (pinfunction "GND6_C18") (pintype "input"))
      (node (ref "U1") (pin "C20") (pinfunction "GND7_C20") (pintype "input"))
      (node (ref "U1") (pin "C6") (pinfunction "GND1_C6") (pintype "input"))
      (node (ref "U1") (pin "C8") (pinfunction "GND2_C8") (pintype "input"))
      (node (ref "U1") (pin "D6") (pinfunction "GND8_D6") (pintype "input"))
      (node (ref "U1") (pin "E3") (pinfunction "GND9_E3") (pintype "input"))
      (node (ref "U1") (pin "F10") (pinfunction "GND12_F10") (pintype "input"))
      (node (ref "U1") (pin "F12") (pinfunction "GND13_F12") (pintype "input"))
      (node (ref "U1") (pin "F6") (pinfunction "GND10_F6") (pintype "input"))
      (node (ref "U1") (pin "F8") (pinfunction "GND11_F8") (pintype "input"))
      (node (ref "U1") (pin "G10") (pinfunction "GND16_G10") (pintype "input"))
      (node (ref "U1") (pin "G14") (pinfunction "GND17_G14") (pintype "input"))
      (node (ref "U1") (pin "G18") (pinfunction "GND18_G18") (pintype "input"))
      (node (ref "U1") (pin "G29") (pinfunction "GND19_G29") (pintype "input"))
      (node (ref "U1") (pin "G3") (pinfunction "GND14_G3") (pintype "input"))
      (node (ref "U1") (pin "G8") (pinfunction "GND15_G8") (pintype "input"))
      (node (ref "U1") (pin "J10") (pinfunction "GND23_J10") (pintype "input"))
      (node (ref "U1") (pin "J12") (pinfunction "GND24_J12") (pintype "input"))
      (node (ref "U1") (pin "J13") (pinfunction "GND25_J13") (pintype "input"))
      (node (ref "U1") (pin "J28") (pinfunction "GND26_J28") (pintype "input"))
      (node (ref "U1") (pin "J3") (pinfunction "GND20_J3") (pintype "input"))
      (node (ref "U1") (pin "J31") (pinfunction "GND27_J31") (pintype "input"))
      (node (ref "U1") (pin "J6") (pinfunction "GND21_J6") (pintype "input"))
      (node (ref "U1") (pin "J9") (pinfunction "GND22_J9") (pintype "input"))
      (node (ref "U1") (pin "K10") (pinfunction "GND29_K10") (pintype "input"))
      (node (ref "U1") (pin "K11") (pinfunction "GND30_K11") (pintype "input"))
      (node (ref "U1") (pin "K12") (pinfunction "GND31_K12") (pintype "input"))
      (node (ref "U1") (pin "K26") (pinfunction "GND32_K26") (pintype "input"))
      (node (ref "U1") (pin "K9") (pinfunction "GND28_K9") (pintype "input"))
      (node (ref "U1") (pin "L10") (pinfunction "GND35_L10") (pintype "input"))
      (node (ref "U1") (pin "L12") (pinfunction "GND36_L12") (pintype "input"))
      (node (ref "U1") (pin "L13") (pinfunction "GND37_L13") (pintype "input"))
      (node (ref "U1") (pin "L27") (pinfunction "GND38_L27") (pintype "input"))
      (node (ref "U1") (pin "L3") (pinfunction "GND33_L3") (pintype "input"))
      (node (ref "U1") (pin "L30") (pinfunction "GND39_L30") (pintype "input"))
      (node (ref "U1") (pin "L33") (pinfunction "GND40_L33") (pintype "input"))
      (node (ref "U1") (pin "L6") (pinfunction "GND34_L6") (pintype "input"))
      (node (ref "U1") (pin "M13") (pinfunction "GND41_M13") (pintype "input"))
      (node (ref "U1") (pin "N10") (pinfunction "GND44_N10") (pintype "input"))
      (node (ref "U1") (pin "N12") (pinfunction "GND45_N12") (pintype "input"))
      (node (ref "U1") (pin "N15") (pinfunction "GND46_N15") (pintype "input"))
      (node (ref "U1") (pin "N18") (pinfunction "GND47_N18") (pintype "input"))
      (node (ref "U1") (pin "N19") (pinfunction "GND48_N19") (pintype "input"))
      (node (ref "U1") (pin "N22") (pinfunction "GND49_N22") (pintype "input"))
      (node (ref "U1") (pin "N26") (pinfunction "GND50_N26") (pintype "input"))
      (node (ref "U1") (pin "N27") (pinfunction "GND51_N27") (pintype "input"))
      (node (ref "U1") (pin "N3") (pinfunction "GND42_N3") (pintype "input"))
      (node (ref "U1") (pin "N30") (pinfunction "GND52_N30") (pintype "input"))
      (node (ref "U1") (pin "N6") (pinfunction "GND43_N6") (pintype "input"))
      (node (ref "U1") (pin "P11") (pinfunction "GND53_P11") (pintype "input"))
      (node (ref "U1") (pin "P16") (pinfunction "GND54_P16") (pintype "input"))
      (node (ref "U1") (pin "P19") (pinfunction "GND55_P19") (pintype "input"))
      (node (ref "U1") (pin "P24") (pinfunction "GND56_P24") (pintype "input"))
      (node (ref "U1") (pin "R11") (pinfunction "GND59_R11") (pintype "input"))
      (node (ref "U1") (pin "R13") (pinfunction "GND60_R13") (pintype "input"))
      (node (ref "U1") (pin "R19") (pinfunction "GND61_R19") (pintype "input"))
      (node (ref "U1") (pin "R24") (pinfunction "GND62_R24") (pintype "input"))
      (node (ref "U1") (pin "R27") (pinfunction "GND63_R27") (pintype "input"))
      (node (ref "U1") (pin "R3") (pinfunction "GND57_R3") (pintype "input"))
      (node (ref "U1") (pin "R7") (pinfunction "GND58_R7") (pintype "input"))
      (node (ref "U1") (pin "T15") (pinfunction "GND64_T15") (pintype "input"))
      (node (ref "U1") (pin "T16") (pinfunction "GND65_T16") (pintype "input"))
      (node (ref "U1") (pin "T18") (pinfunction "GND66_T18") (pintype "input"))
      (node (ref "U1") (pin "T24") (pinfunction "GND67_T24") (pintype "input"))
      (node (ref "U1") (pin "U14") (pinfunction "GND69_U14") (pintype "input"))
      (node (ref "U1") (pin "U16") (pinfunction "GND70_U16") (pintype "input"))
      (node (ref "U1") (pin "U25") (pinfunction "GND71_U25") (pintype "input"))
      (node (ref "U1") (pin "U27") (pinfunction "GND72_U27") (pintype "input"))
      (node (ref "U1") (pin "U7") (pinfunction "GND68_U7") (pintype "input"))
      (node (ref "U1") (pin "V18") (pinfunction "GND73_V18") (pintype "input"))
      (node (ref "U1") (pin "V19") (pinfunction "GND74_V19") (pintype "input"))
      (node (ref "U1") (pin "W12") (pinfunction "GND75_W12") (pintype "input"))
      (node (ref "U1") (pin "W13") (pinfunction "GND76_W13") (pintype "input"))
      (node (ref "U1") (pin "W15") (pinfunction "GND77_W15") (pintype "input"))
      (node (ref "U1") (pin "W16") (pinfunction "GND78_W16") (pintype "input"))
      (node (ref "U1") (pin "W22") (pinfunction "GND79_W22") (pintype "input"))
      (node (ref "U1") (pin "W27") (pinfunction "GND80_W27") (pintype "input"))
      (node (ref "U1") (pin "W30") (pinfunction "GND81_W30") (pintype "input"))
      (node (ref "U1") (pin "Y15") (pinfunction "GND82_Y15") (pintype "input"))
      (node (ref "U1") (pin "Y18") (pinfunction "GND83_Y18") (pintype "input"))
      (node (ref "U1") (pin "Y22") (pinfunction "GND84_Y22") (pintype "input"))
      (node (ref "U1") (pin "Y23") (pinfunction "GND85_Y23") (pintype "input"))
      (node (ref "U1") (pin "Y26") (pinfunction "GND86_Y26") (pintype "input"))
      (node (ref "UD1") (pin "A10") (pinfunction "VSS1_A10") (pintype "input"))
      (node (ref "UD1") (pin "A3") (pinfunction "VSS0_A3") (pintype "input"))
      (node (ref "UD1") (pin "AB10") (pinfunction "VSS57_AB10") (pintype "input"))
      (node (ref "UD1") (pin "AB3") (pinfunction "VSS54_AB3") (pintype "input"))
      (node (ref "UD1") (pin "AB5") (pinfunction "VSS55_AB5") (pintype "input"))
      (node (ref "UD1") (pin "AB8") (pinfunction "VSS56_AB8") (pintype "input"))
      (node (ref "UD1") (pin "C1") (pinfunction "VSS2_C1") (pintype "input"))
      (node (ref "UD1") (pin "C12") (pinfunction "VSS5_C12") (pintype "input"))
      (node (ref "UD1") (pin "C5") (pinfunction "VSS3_C5") (pintype "input"))
      (node (ref "UD1") (pin "C8") (pinfunction "VSS4_C8") (pintype "input"))
      (node (ref "UD1") (pin "D11") (pinfunction "VSS9_D11") (pintype "input"))
      (node (ref "UD1") (pin "D2") (pinfunction "VSS6_D2") (pintype "input"))
      (node (ref "UD1") (pin "D4") (pinfunction "VSS7_D4") (pintype "input"))
      (node (ref "UD1") (pin "D9") (pinfunction "VSS8_D9") (pintype "input"))
      (node (ref "UD1") (pin "E1") (pinfunction "VSS10_E1") (pintype "input"))
      (node (ref "UD1") (pin "E12") (pinfunction "VSS13_E12") (pintype "input"))
      (node (ref "UD1") (pin "E5") (pinfunction "VSS11_E5") (pintype "input"))
      (node (ref "UD1") (pin "E8") (pinfunction "VSS12_E8") (pintype "input"))
      (node (ref "UD1") (pin "G1") (pinfunction "VSS14_G1") (pintype "input"))
      (node (ref "UD1") (pin "G10") (pinfunction "VSS18_G10") (pintype "input"))
      (node (ref "UD1") (pin "G12") (pinfunction "VSS19_G12") (pintype "input"))
      (node (ref "UD1") (pin "G3") (pinfunction "VSS15_G3") (pintype "input"))
      (node (ref "UD1") (pin "G5") (pinfunction "VSS16_G5") (pintype "input"))
      (node (ref "UD1") (pin "G8") (pinfunction "VSS17_G8") (pintype "input"))
      (node (ref "UD1") (pin "J1") (pinfunction "VSS20_J1") (pintype "input"))
      (node (ref "UD1") (pin "J10") (pinfunction "VSS22_J10") (pintype "input"))
      (node (ref "UD1") (pin "J12") (pinfunction "VSS23_J12") (pintype "input"))
      (node (ref "UD1") (pin "J3") (pinfunction "VSS21_J3") (pintype "input"))
      (node (ref "UD1") (pin "K11") (pinfunction "VSS27_K11") (pintype "input"))
      (node (ref "UD1") (pin "K2") (pinfunction "VSS24_K2") (pintype "input"))
      (node (ref "UD1") (pin "K4") (pinfunction "VSS25_K4") (pintype "input"))
      (node (ref "UD1") (pin "K9") (pinfunction "VSS26_K9") (pintype "input"))
      (node (ref "UD1") (pin "N11") (pinfunction "VSS31_N11") (pintype "input"))
      (node (ref "UD1") (pin "N2") (pinfunction "VSS28_N2") (pintype "input"))
      (node (ref "UD1") (pin "N4") (pinfunction "VSS29_N4") (pintype "input"))
      (node (ref "UD1") (pin "N9") (pinfunction "VSS30_N9") (pintype "input"))
      (node (ref "UD1") (pin "P1") (pinfunction "VSS32_P1") (pintype "input"))
      (node (ref "UD1") (pin "P10") (pinfunction "VSS34_P10") (pintype "input"))
      (node (ref "UD1") (pin "P12") (pinfunction "VSS35_P12") (pintype "input"))
      (node (ref "UD1") (pin "P3") (pinfunction "VSS33_P3") (pintype "input"))
      (node (ref "UD1") (pin "T1") (pinfunction "VSS36_T1") (pintype "input"))
      (node (ref "UD1") (pin "T10") (pinfunction "VSS40_T10") (pintype "input"))
      (node (ref "UD1") (pin "T12") (pinfunction "VSS41_T12") (pintype "input"))
      (node (ref "UD1") (pin "T3") (pinfunction "VSS37_T3") (pintype "input"))
      (node (ref "UD1") (pin "T5") (pinfunction "VSS38_T5") (pintype "input"))
      (node (ref "UD1") (pin "T8") (pinfunction "VSS39_T8") (pintype "input"))
      (node (ref "UD1") (pin "V1") (pinfunction "VSS42_V1") (pintype "input"))
      (node (ref "UD1") (pin "V12") (pinfunction "VSS45_V12") (pintype "input"))
      (node (ref "UD1") (pin "V5") (pinfunction "VSS43_V5") (pintype "input"))
      (node (ref "UD1") (pin "V8") (pinfunction "VSS44_V8") (pintype "input"))
      (node (ref "UD1") (pin "W11") (pinfunction "VSS49_W11") (pintype "input"))
      (node (ref "UD1") (pin "W2") (pinfunction "VSS46_W2") (pintype "input"))
      (node (ref "UD1") (pin "W4") (pinfunction "VSS47_W4") (pintype "input"))
      (node (ref "UD1") (pin "W9") (pinfunction "VSS48_W9") (pintype "input"))
      (node (ref "UD1") (pin "Y1") (pinfunction "VSS50_Y1") (pintype "input"))
      (node (ref "UD1") (pin "Y12") (pinfunction "VSS53_Y12") (pintype "input"))
      (node (ref "UD1") (pin "Y5") (pinfunction "VSS51_Y5") (pintype "input"))
      (node (ref "UD1") (pin "Y8") (pinfunction "VSS52_Y8") (pintype "input"))
    )
    (net (code "71") (name "Net-(U1A-SZQ)") (class "Default")
      (node (ref "R3") (pin "1") (pinfunction "1_1") (pintype "input"))
      (node (ref "U1") (pin "AA29") (pinfunction "SZQ_AA29") (pintype "input"))
    )
    (net (code "72") (name "Net-(UD1A-ODT_CA_A)") (class "Default")
      (node (ref "R1") (pin "1") (pinfunction "1_1") (pintype "input"))
      (node (ref "UD1") (pin "G2") (pinfunction "ODT_CA_A_G2") (pintype "input"))
    )
    (net (code "73") (name "Net-(UD1A-ODT_CA_B)") (class "Default")
      (node (ref "R2") (pin "1") (pinfunction "1_1") (pintype "input"))
      (node (ref "UD1") (pin "T2") (pinfunction "ODT_CA_B_T2") (pintype "input"))
    )
    (net (code "74") (name "Net-(UD1A-ZQ0)") (class "Default")
      (node (ref "R4") (pin "1") (pinfunction "1_1") (pintype "input"))
      (node (ref "UD1") (pin "A5") (pinfunction "ZQ0_A5") (pintype "input"))
    )
    (net (code "75") (name "Net-(UD1A-ZQ1)") (class "Default")
      (node (ref "R5") (pin "1") (pinfunction "1_1") (pintype "input"))
      (node (ref "UD1") (pin "A8") (pinfunction "ZQ1_A8") (pintype "input"))
    )
    (net (code "76") (name "VCC-DRAM") (class "Default")
      (node (ref "C1") (pin "1") (pinfunction "1_1") (pintype "input"))
      (node (ref "C10") (pin "2") (pinfunction "2_2") (pintype "input"))
      (node (ref "C11") (pin "2") (pinfunction "2_2") (pintype "input"))
      (node (ref "C12") (pin "2") (pinfunction "2_2") (pintype "input"))
      (node (ref "C13") (pin "2") (pinfunction "2_2") (pintype "input"))
      (node (ref "C14") (pin "2") (pinfunction "2_2") (pintype "input"))
      (node (ref "C15") (pin "2") (pinfunction "2_2") (pintype "input"))
      (node (ref "C16") (pin "2") (pinfunction "2_2") (pintype "input"))
      (node (ref "C2") (pin "1") (pinfunction "1_1") (pintype "input"))
      (node (ref "C27") (pin "1") (pinfunction "1_1") (pintype "input"))
      (node (ref "C28") (pin "1") (pinfunction "1_1") (pintype "input"))
      (node (ref "C29") (pin "2") (pinfunction "2_2") (pintype "input"))
      (node (ref "C3") (pin "2") (pinfunction "2_2") (pintype "input"))
      (node (ref "C30") (pin "2") (pinfunction "2_2") (pintype "input"))
      (node (ref "C31") (pin "2") (pinfunction "2_2") (pintype "input"))
      (node (ref "C32") (pin "1") (pinfunction "1_1") (pintype "input"))
      (node (ref "C33") (pin "2") (pinfunction "2_2") (pintype "input"))
      (node (ref "C34") (pin "2") (pinfunction "2_2") (pintype "input"))
      (node (ref "C35") (pin "2") (pinfunction "2_2") (pintype "input"))
      (node (ref "C36") (pin "2") (pinfunction "2_2") (pintype "input"))
      (node (ref "C37") (pin "2") (pinfunction "2_2") (pintype "input"))
      (node (ref "C38") (pin "2") (pinfunction "2_2") (pintype "input"))
      (node (ref "C39") (pin "2") (pinfunction "2_2") (pintype "input"))
      (node (ref "C4") (pin "2") (pinfunction "2_2") (pintype "input"))
      (node (ref "C40") (pin "2") (pinfunction "2_2") (pintype "input"))
      (node (ref "C41") (pin "2") (pinfunction "2_2") (pintype "input"))
      (node (ref "C42") (pin "2") (pinfunction "2_2") (pintype "input"))
      (node (ref "C43") (pin "2") (pinfunction "2_2") (pintype "input"))
      (node (ref "C44") (pin "2") (pinfunction "2_2") (pintype "input"))
      (node (ref "C45") (pin "2") (pinfunction "2_2") (pintype "input"))
      (node (ref "C5") (pin "2") (pinfunction "2_2") (pintype "input"))
      (node (ref "C6") (pin "2") (pinfunction "2_2") (pintype "input"))
      (node (ref "C7") (pin "2") (pinfunction "2_2") (pintype "input"))
      (node (ref "C8") (pin "2") (pinfunction "2_2") (pintype "input"))
      (node (ref "C9") (pin "2") (pinfunction "2_2") (pintype "input"))
      (node (ref "R1") (pin "2") (pinfunction "2_2") (pintype "input"))
      (node (ref "R2") (pin "2") (pinfunction "2_2") (pintype "input"))
      (node (ref "R3") (pin "2") (pinfunction "2_2") (pintype "input"))
      (node (ref "R4") (pin "2") (pinfunction "2_2") (pintype "input"))
      (node (ref "R5") (pin "2") (pinfunction "2_2") (pintype "input"))
      (node (ref "U1") (pin "AA24") (pinfunction "VCC-DRAM4_AA24") (pintype "input"))
      (node (ref "U1") (pin "AB24") (pinfunction "VCC-DRAM5_AB24") (pintype "input"))
      (node (ref "U1") (pin "AC17") (pinfunction "VCC-DRAML0_AC17") (pintype "input"))
      (node (ref "U1") (pin "AC18") (pinfunction "VCC-DRAML1_AC18") (pintype "input"))
      (node (ref "U1") (pin "AC19") (pinfunction "VCC-DRAML2_AC19") (pintype "input"))
      (node (ref "U1") (pin "AC20") (pinfunction "VCC-DRAML3_AC20") (pintype "input"))
      (node (ref "U1") (pin "AC22") (pinfunction "VCC-DRAML4_AC22") (pintype "input"))
      (node (ref "U1") (pin "AC24") (pinfunction "VCC-DRAM6_AC24") (pintype "input"))
      (node (ref "U1") (pin "W23") (pinfunction "VCC-DRAM0_W23") (pintype "input"))
      (node (ref "U1") (pin "W24") (pinfunction "VCC-DRAM1_W24") (pintype "input"))
      (node (ref "U1") (pin "W25") (pinfunction "VCC-DRAM2_W25") (pintype "input"))
      (node (ref "U1") (pin "Y24") (pinfunction "VCC-DRAM3_Y24") (pintype "input"))
      (node (ref "UD1") (pin "A4") (pinfunction "VDD2-0_A4") (pintype "input"))
      (node (ref "UD1") (pin "A9") (pinfunction "VDD2-1_A9") (pintype "input"))
      (node (ref "UD1") (pin "AA10") (pinfunction "VDDQ-19_AA10") (pintype "input"))
      (node (ref "UD1") (pin "AA3") (pinfunction "VDDQ-16_AA3") (pintype "input"))
      (node (ref "UD1") (pin "AA5") (pinfunction "VDDQ-17_AA5") (pintype "input"))
      (node (ref "UD1") (pin "AA8") (pinfunction "VDDQ-18_AA8") (pintype "input"))
      (node (ref "UD1") (pin "AB4") (pinfunction "VDD2-22_AB4") (pintype "input"))
      (node (ref "UD1") (pin "AB9") (pinfunction "VDD2-23_AB9") (pintype "input"))
      (node (ref "UD1") (pin "B10") (pinfunction "VDDQ-3_B10") (pintype "input"))
      (node (ref "UD1") (pin "B3") (pinfunction "VDDQ-0_B3") (pintype "input"))
      (node (ref "UD1") (pin "B5") (pinfunction "VDDQ-1_B5") (pintype "input"))
      (node (ref "UD1") (pin "B8") (pinfunction "VDDQ-2_B8") (pintype "input"))
      (node (ref "UD1") (pin "D1") (pinfunction "VDDQ-4_D1") (pintype "input"))
      (node (ref "UD1") (pin "D12") (pinfunction "VDDQ-7_D12") (pintype "input"))
      (node (ref "UD1") (pin "D5") (pinfunction "VDDQ-5_D5") (pintype "input"))
      (node (ref "UD1") (pin "D8") (pinfunction "VDDQ-6_D8") (pintype "input"))
      (node (ref "UD1") (pin "F10") (pinfunction "VDDQ-9_F10") (pintype "input"))
      (node (ref "UD1") (pin "F3") (pinfunction "VDDQ-8_F3") (pintype "input"))
      (node (ref "UD1") (pin "F5") (pinfunction "VDD2-2_F5") (pintype "input"))
      (node (ref "UD1") (pin "F8") (pinfunction "VDD2-3_F8") (pintype "input"))
      (node (ref "UD1") (pin "H1") (pinfunction "VDD2-4_H1") (pintype "input"))
      (node (ref "UD1") (pin "H12") (pinfunction "VDD2-7_H12") (pintype "input"))
      (node (ref "UD1") (pin "H5") (pinfunction "VDD2-5_H5") (pintype "input"))
      (node (ref "UD1") (pin "H8") (pinfunction "VDD2-6_H8") (pintype "input"))
      (node (ref "UD1") (pin "K1") (pinfunction "VDD2-8_K1") (pintype "input"))
      (node (ref "UD1") (pin "K10") (pinfunction "VDD2-10_K10") (pintype "input"))
      (node (ref "UD1") (pin "K12") (pinfunction "VDD2-11_K12") (pintype "input"))
      (node (ref "UD1") (pin "K3") (pinfunction "VDD2-9_K3") (pintype "input"))
      (node (ref "UD1") (pin "N1") (pinfunction "VDD2-12_N1") (pintype "input"))
      (node (ref "UD1") (pin "N10") (pinfunction "VDD2-14_N10") (pintype "input"))
      (node (ref "UD1") (pin "N12") (pinfunction "VDD2-15_N12") (pintype "input"))
      (node (ref "UD1") (pin "N3") (pinfunction "VDD2-13_N3") (pintype "input"))
      (node (ref "UD1") (pin "R1") (pinfunction "VDD2-16_R1") (pintype "input"))
      (node (ref "UD1") (pin "R12") (pinfunction "VDD2-19_R12") (pintype "input"))
      (node (ref "UD1") (pin "R5") (pinfunction "VDD2-17_R5") (pintype "input"))
      (node (ref "UD1") (pin "R8") (pinfunction "VDD2-18_R8") (pintype "input"))
      (node (ref "UD1") (pin "U10") (pinfunction "VDDQ-11_U10") (pintype "input"))
      (node (ref "UD1") (pin "U3") (pinfunction "VDDQ-10_U3") (pintype "input"))
      (node (ref "UD1") (pin "U5") (pinfunction "VDD2-20_U5") (pintype "input"))
      (node (ref "UD1") (pin "U8") (pinfunction "VDD2-21_U8") (pintype "input"))
      (node (ref "UD1") (pin "W1") (pinfunction "VDDQ-12_W1") (pintype "input"))
      (node (ref "UD1") (pin "W12") (pinfunction "VDDQ-15_W12") (pintype "input"))
      (node (ref "UD1") (pin "W5") (pinfunction "VDDQ-13_W5") (pintype "input"))
      (node (ref "UD1") (pin "W8") (pinfunction "VDDQ-14_W8") (pintype "input"))
    )
    (net (code "77") (name "VDD18-DRAM") (class "Default")
      (node (ref "C17") (pin "1") (pinfunction "1_1") (pintype "input"))
      (node (ref "C18") (pin "2") (pinfunction "2_2") (pintype "input"))
      (node (ref "C46") (pin "1") (pinfunction "1_1") (pintype "input"))
      (node (ref "C47") (pin "2") (pinfunction "2_2") (pintype "input"))
      (node (ref "U1") (pin "AD25") (pinfunction "VDD18-DRAM_AD25") (pintype "input"))
    )
    (net (code "78") (name "VDD18-LPDDR") (class "Default")
      (node (ref "C19") (pin "1") (pinfunction "1_1") (pintype "input"))
      (node (ref "C20") (pin "2") (pinfunction "2_2") (pintype "input"))
      (node (ref "C21") (pin "2") (pinfunction "2_2") (pintype "input"))
      (node (ref "C22") (pin "2") (pinfunction "2_2") (pintype "input"))
      (node (ref "C23") (pin "2") (pinfunction "2_2") (pintype "input"))
      (node (ref "C24") (pin "2") (pinfunction "2_2") (pintype "input"))
      (node (ref "C25") (pin "2") (pinfunction "2_2") (pintype "input"))
      (node (ref "C26") (pin "2") (pinfunction "2_2") (pintype "input"))
      (node (ref "UD1") (pin "F1") (pinfunction "VDD1-0_F1") (pintype "input"))
      (node (ref "UD1") (pin "F12") (pinfunction "VDD1-1_F12") (pintype "input"))
      (node (ref "UD1") (pin "G4") (pinfunction "VDD1-2_G4") (pintype "input"))
      (node (ref "UD1") (pin "G9") (pinfunction "VDD1-3_G9") (pintype "input"))
      (node (ref "UD1") (pin "T4") (pinfunction "VDD1-4_T4") (pintype "input"))
      (node (ref "UD1") (pin "T9") (pinfunction "VDD1-5_T9") (pintype "input"))
      (node (ref "UD1") (pin "U1") (pinfunction "VDD1-6_U1") (pintype "input"))
      (node (ref "UD1") (pin "U12") (pinfunction "VDD1-7_U12") (pintype "input"))
    )
    (net (code "79") (name "unconnected-(U1A-SA0-PadAK33)") (class "Default")
      (node (ref "U1") (pin "AK33") (pinfunction "SA0_AK33") (pintype "input+no_connect"))
    )
    (net (code "80") (name "unconnected-(U1A-SA3-PadAL27)") (class "Default")
      (node (ref "U1") (pin "AL27") (pinfunction "SA3_AL27") (pintype "input+no_connect"))
    )
    (net (code "81") (name "unconnected-(U1A-SA7-PadAM33)") (class "Default")
      (node (ref "U1") (pin "AM33") (pinfunction "SA7_AM33") (pintype "input+no_connect"))
    )
    (net (code "82") (name "unconnected-(U1A-SBG0-PadAN26)") (class "Default")
      (node (ref "U1") (pin "AN26") (pinfunction "SBG0_AN26") (pintype "input+no_connect"))
    )
    (net (code "83") (name "unconnected-(U1A-SODT0-PadAL32)") (class "Default")
      (node (ref "U1") (pin "AL32") (pinfunction "SODT0_AL32") (pintype "input+no_connect"))
    )
    (net (code "84") (name "unconnected-(U1A-SODT1-PadAL33)") (class "Default")
      (node (ref "U1") (pin "AL33") (pinfunction "SODT1_AL33") (pintype "input+no_connect"))
    )
    (net (code "85") (name "unconnected-(UD1B-NC0-PadA1)") (class "Default")
      (node (ref "UD1") (pin "A1") (pinfunction "NC0_A1") (pintype "input+no_connect"))
    )
    (net (code "86") (name "unconnected-(UD1B-NC1-PadA2)") (class "Default")
      (node (ref "UD1") (pin "A2") (pinfunction "NC1_A2") (pintype "input+no_connect"))
    )
    (net (code "87") (name "unconnected-(UD1B-NC2-PadA11)") (class "Default")
      (node (ref "UD1") (pin "A11") (pinfunction "NC2_A11") (pintype "input+no_connect"))
    )
    (net (code "88") (name "unconnected-(UD1B-NC3-PadA12)") (class "Default")
      (node (ref "UD1") (pin "A12") (pinfunction "NC3_A12") (pintype "input+no_connect"))
    )
    (net (code "89") (name "unconnected-(UD1B-NC4-PadB1)") (class "Default")
      (node (ref "UD1") (pin "B1") (pinfunction "NC4_B1") (pintype "input+no_connect"))
    )
    (net (code "90") (name "unconnected-(UD1B-NC5-PadB12)") (class "Default")
      (node (ref "UD1") (pin "B12") (pinfunction "NC5_B12") (pintype "input+no_connect"))
    )
    (net (code "91") (name "unconnected-(UD1B-NC6-PadG11)") (class "Default")
      (node (ref "UD1") (pin "G11") (pinfunction "NC6_G11") (pintype "input+no_connect"))
    )
    (net (code "92") (name "unconnected-(UD1B-NC7-PadK5)") (class "Default")
      (node (ref "UD1") (pin "K5") (pinfunction "NC7_K5") (pintype "input+no_connect"))
    )
    (net (code "93") (name "unconnected-(UD1B-NC8-PadK8)") (class "Default")
      (node (ref "UD1") (pin "K8") (pinfunction "NC8_K8") (pintype "input+no_connect"))
    )
    (net (code "94") (name "unconnected-(UD1B-NC9-PadN5)") (class "Default")
      (node (ref "UD1") (pin "N5") (pinfunction "NC9_N5") (pintype "input+no_connect"))
    )
    (net (code "95") (name "unconnected-(UD1B-NC10-PadN8)") (class "Default")
      (node (ref "UD1") (pin "N8") (pinfunction "NC10_N8") (pintype "input+no_connect"))
    )
    (net (code "96") (name "unconnected-(UD1B-NC11-PadAA1)") (class "Default")
      (node (ref "UD1") (pin "AA1") (pinfunction "NC11_AA1") (pintype "input+no_connect"))
    )
    (net (code "97") (name "unconnected-(UD1B-NC12-PadAA12)") (class "Default")
      (node (ref "UD1") (pin "AA12") (pinfunction "NC12_AA12") (pintype "input+no_connect"))
    )
    (net (code "98") (name "unconnected-(UD1B-NC13-PadAB1)") (class "Default")
      (node (ref "UD1") (pin "AB1") (pinfunction "NC13_AB1") (pintype "input+no_connect"))
    )
    (net (code "99") (name "unconnected-(UD1B-NC14-PadAB2)") (class "Default")
      (node (ref "UD1") (pin "AB2") (pinfunction "NC14_AB2") (pintype "input+no_connect"))
    )
    (net (code "100") (name "unconnected-(UD1B-NC15-PadAB11)") (class "Default")
      (node (ref "UD1") (pin "AB11") (pinfunction "NC15_AB11") (pintype "input+no_connect"))
    )
    (net (code "101") (name "unconnected-(UD1B-NC16-PadAB12)") (class "Default")
      (node (ref "UD1") (pin "AB12") (pinfunction "NC16_AB12") (pintype "input+no_connect"))
    )
  )
)
